# 06_-_Sensor.net
KiCad netlist of a schematic drawn in Altium Designer
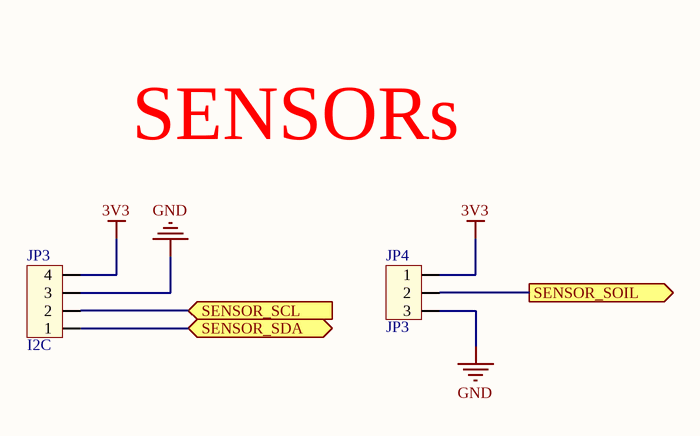
[diagram p0: [06] - Sensor.SchDoc]

(export (version "E")
  (design (tool "Eeschema 10.0.6"))
  (components
    (comp (ref "JP3")
      (value "I2C")
      (footprint "CON4")
      (description "Connector 4")
      (libsource (lib "My Library") (part "Con4"))
    )
    (comp (ref "JP4")
      (value "JP3")
      (footprint "CON3")
      (description "Connector 3")
      (libsource (lib "My Library") (part "Con3"))
    )
  )
  (nets
    (net (code "1") (name "/SENSOR_SCL") (class "Default")
      (node (ref "JP3") (pin "2") (pinfunction "2_2") (pintype "passive"))
    )
    (net (code "2") (name "/SENSOR_SDA") (class "Default")
      (node (ref "JP3") (pin "1") (pinfunction "1_1") (pintype "passive"))
    )
    (net (code "3") (name "/SENSOR_SOIL") (class "Default")
      (node (ref "JP4") (pin "2") (pinfunction "2_2") (pintype "passive"))
    )
    (net (code "4") (name "3V3") (class "Default")
      (node (ref "JP3") (pin "4") (pinfunction "4_4") (pintype "passive"))
      (node (ref "JP4") (pin "1") (pinfunction "1_1") (pintype "passive"))
    )
    (net (code "5") (name "GND") (class "Default")
      (node (ref "JP3") (pin "3") (pinfunction "3_3") (pintype "passive"))
      (node (ref "JP4") (pin "3") (pinfunction "3_3") (pintype "passive"))
    )
  )
)
